# PCB-CMB-2b.net
KiCad netlist of a schematic drawn in EAGLE
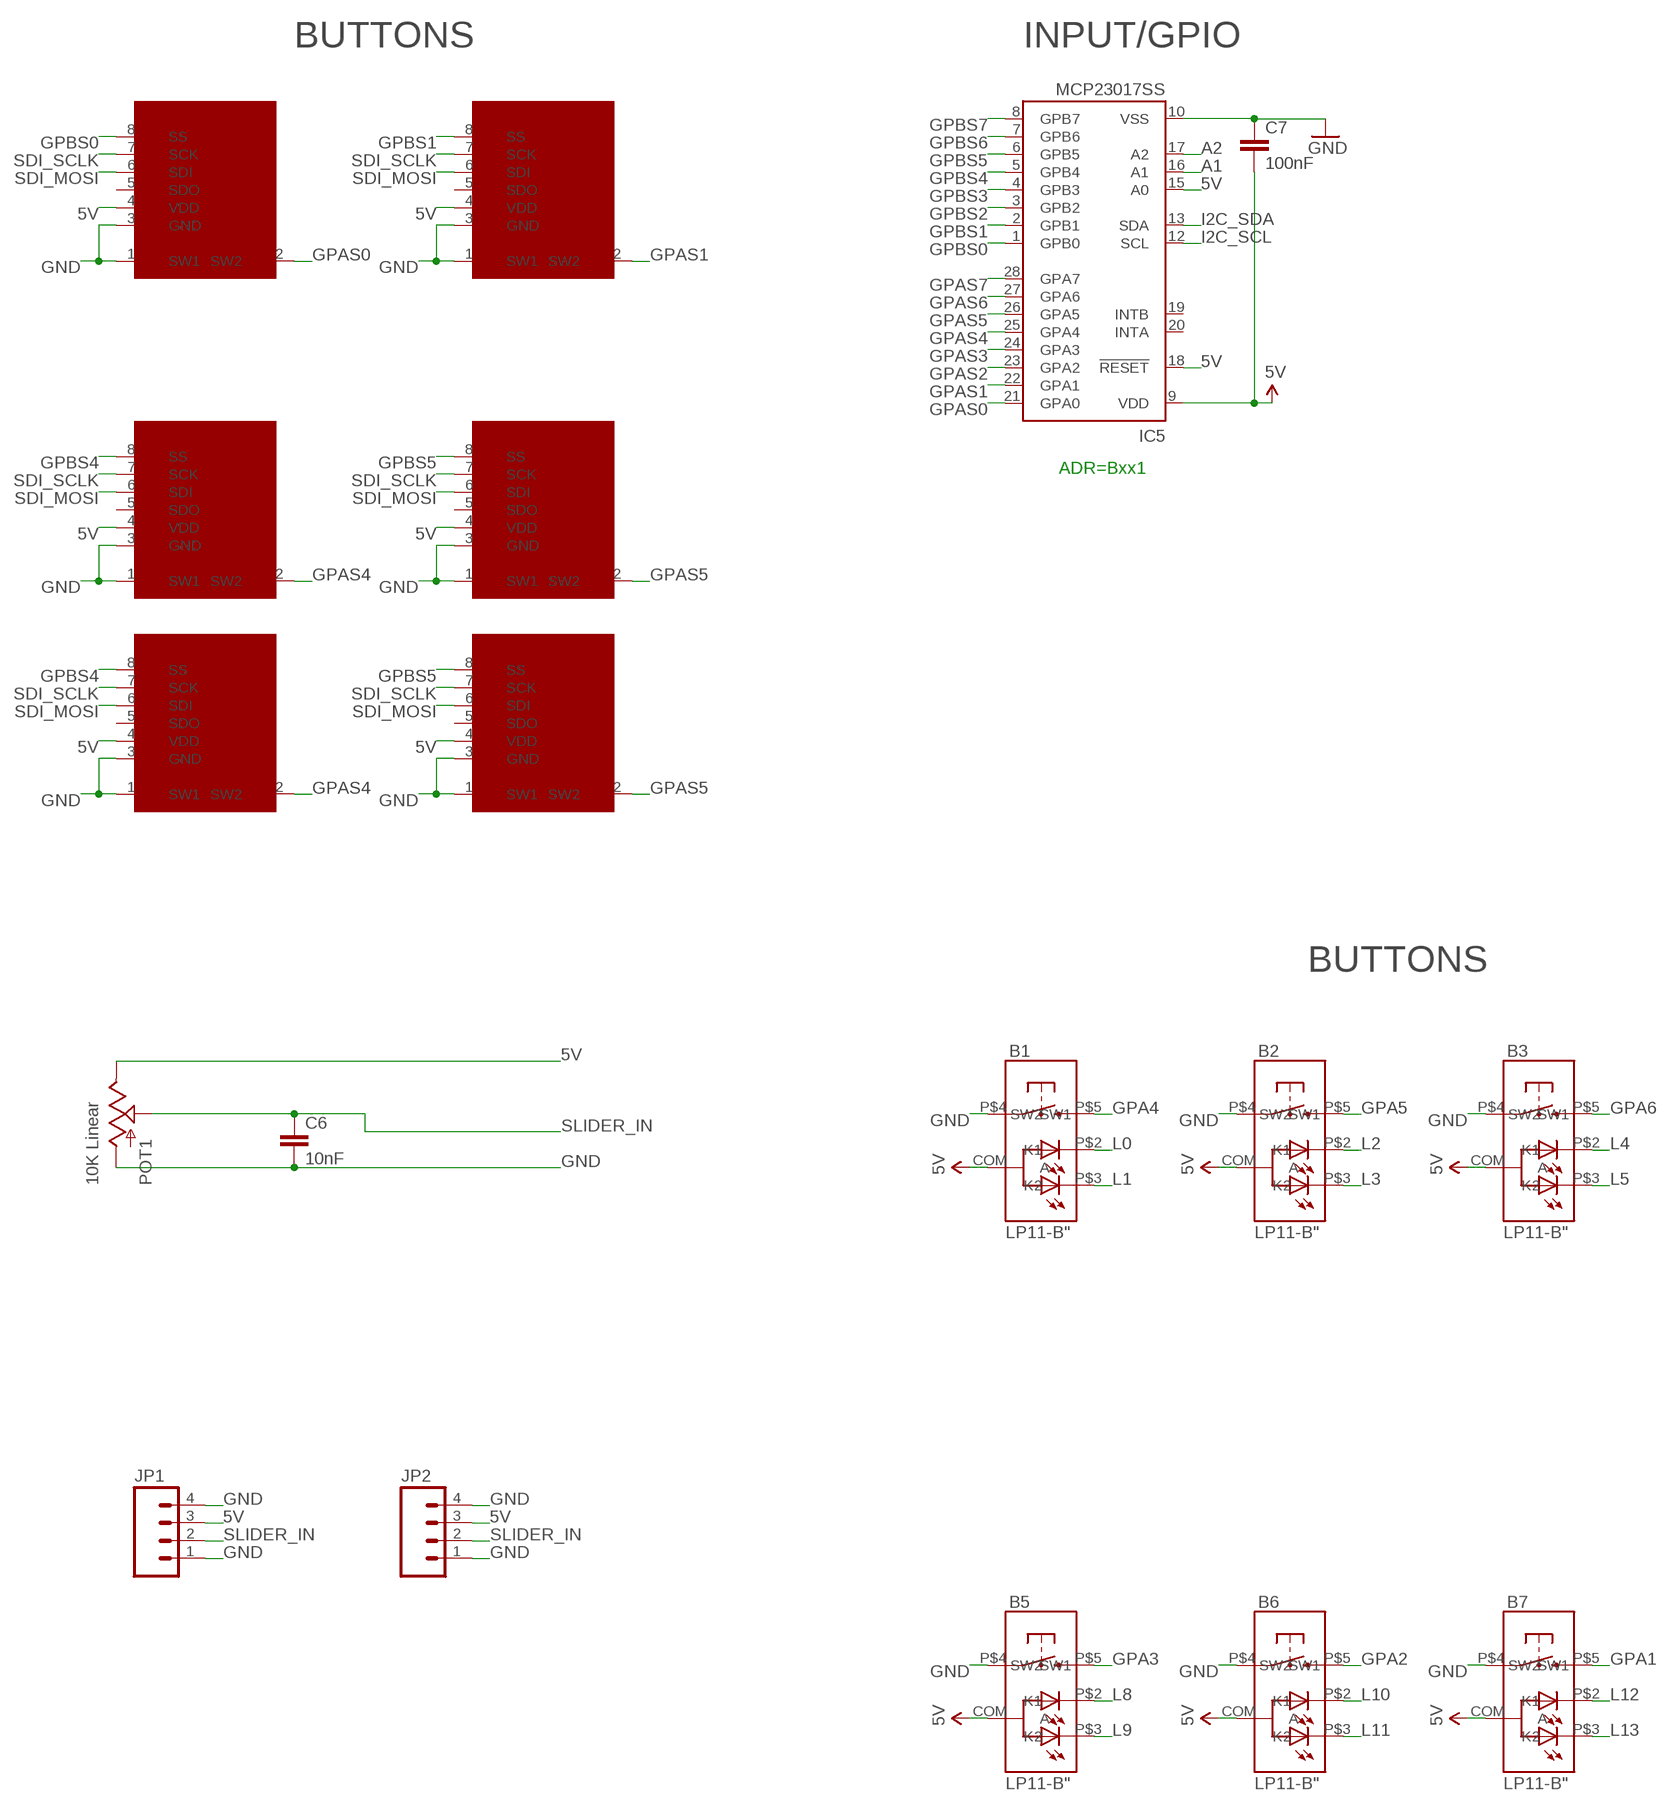
[diagram p0: schematic, sheet 1, part 1 of 2]
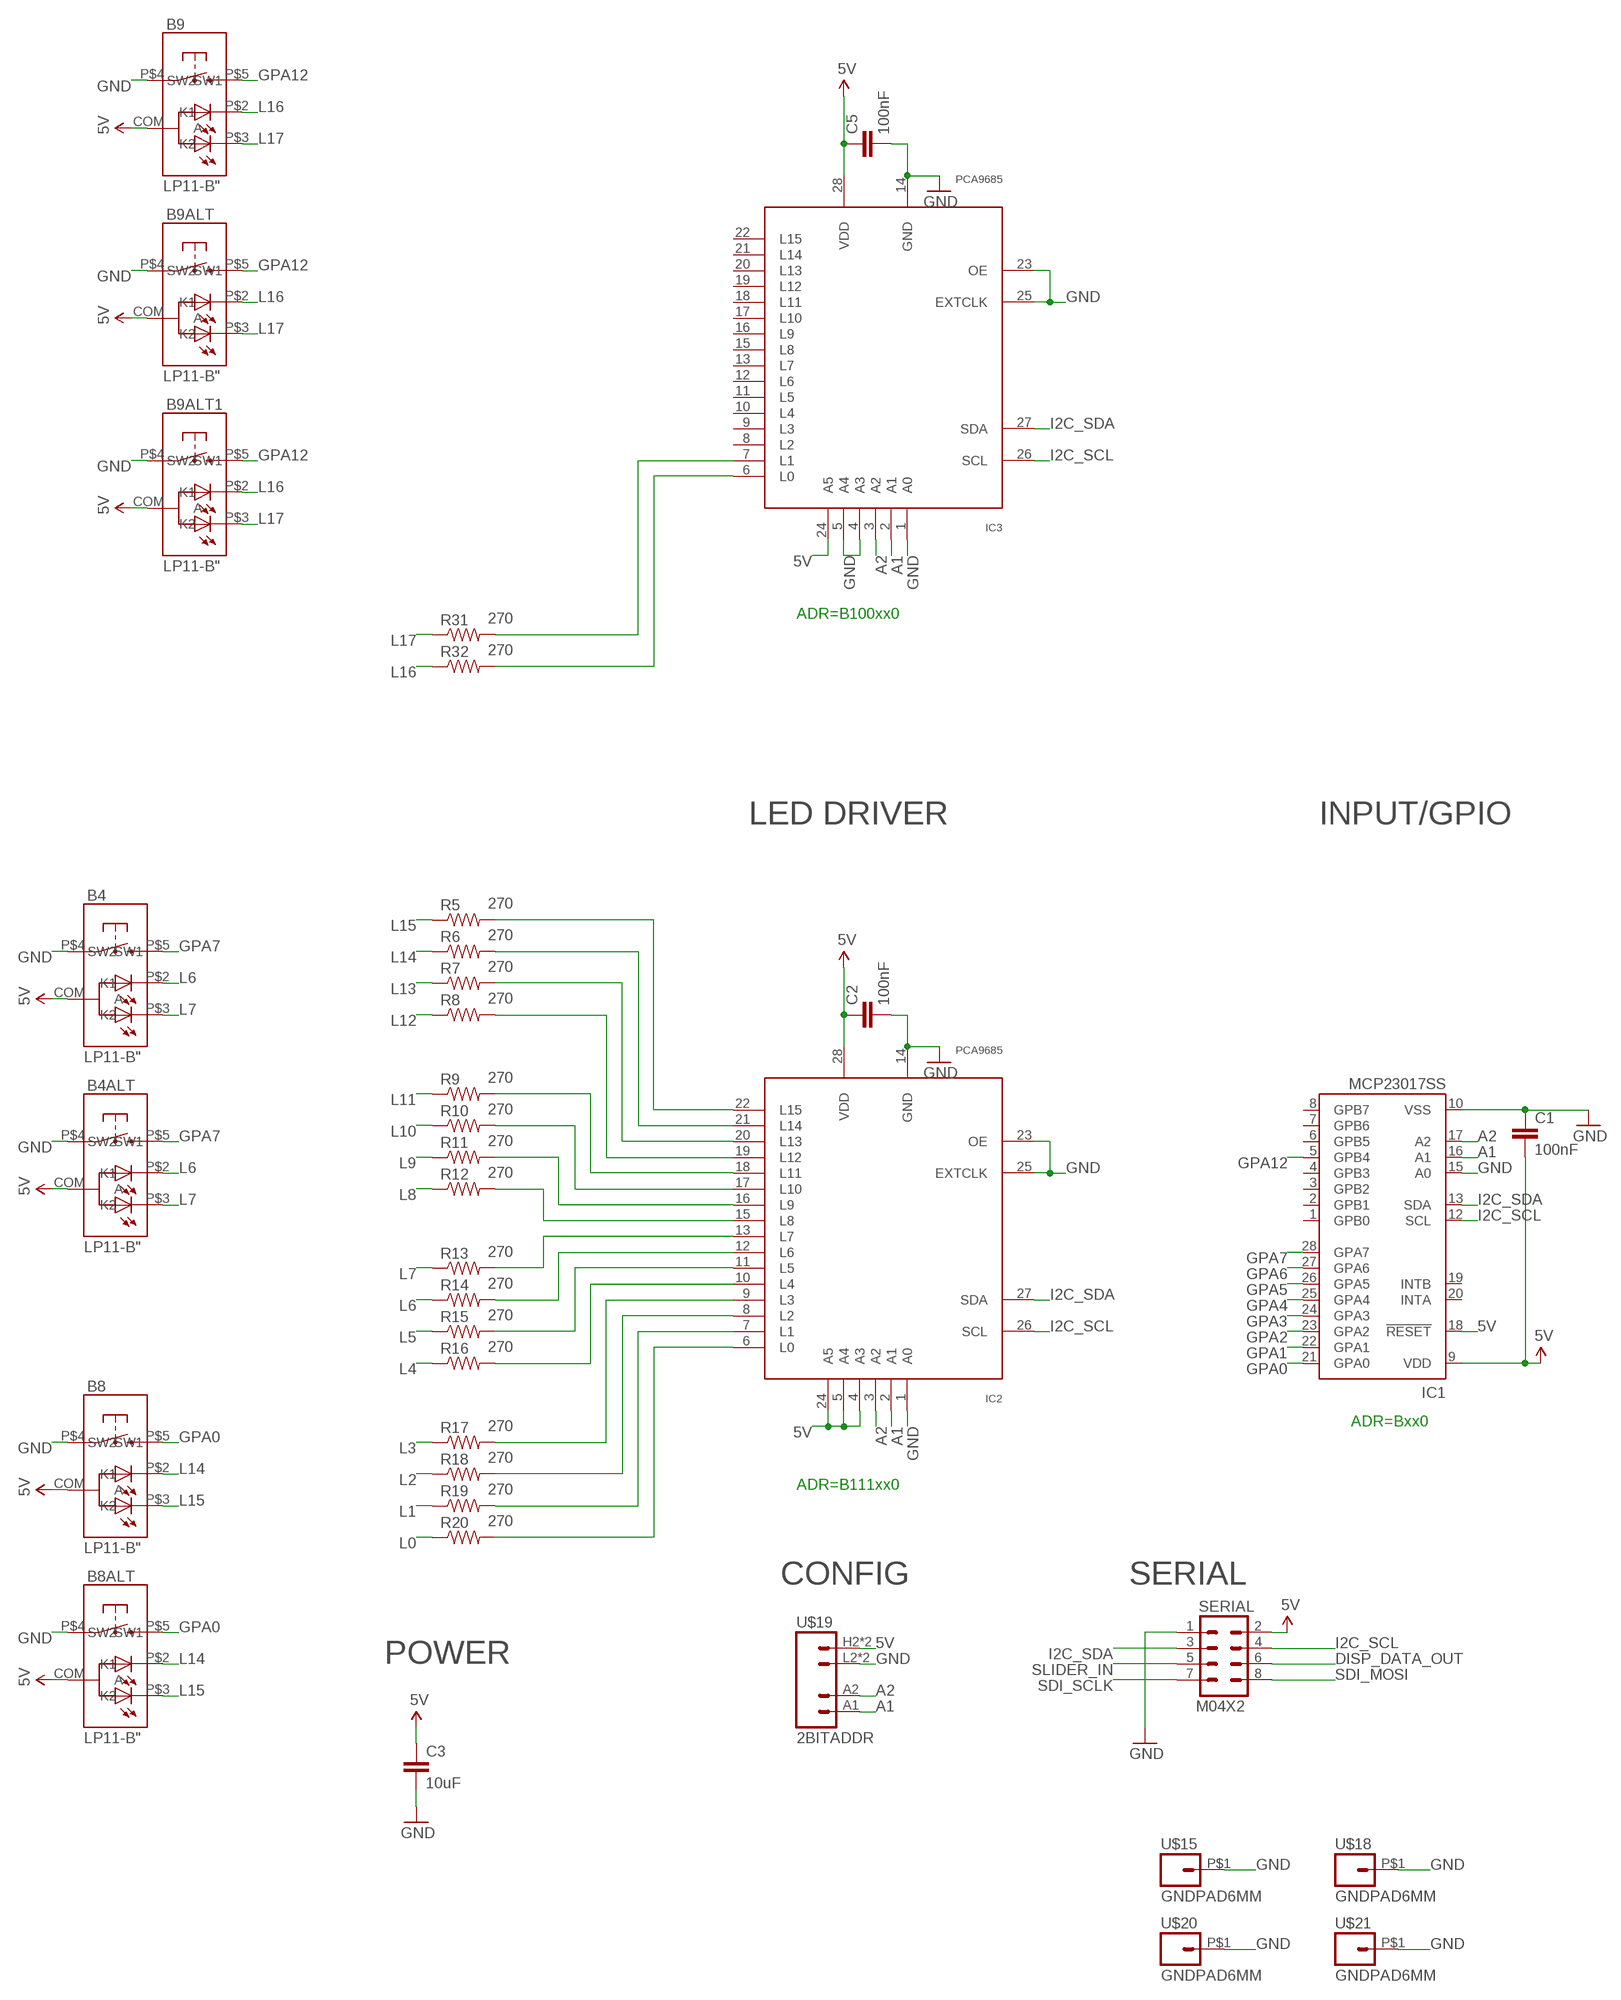
[diagram p1: schematic, sheet 1, part 2 of 2]

(export (version "E")
  (design (tool "Eeschema 10.0.6"))
  (components
    (comp (ref "B1")
      (value "LP11-B\"")
      (footprint "eagle-import:LP11")
      (libsource (lib "eagle-import") (part "LP11-B{dblquote}"))
    )
    (comp (ref "B2")
      (value "LP11-B\"")
      (footprint "eagle-import:LP11")
      (libsource (lib "eagle-import") (part "LP11-B{dblquote}"))
    )
    (comp (ref "B3")
      (value "LP11-B\"")
      (footprint "eagle-import:LP11")
      (libsource (lib "eagle-import") (part "LP11-B{dblquote}"))
    )
    (comp (ref "B4")
      (value "LP11-B\"")
      (footprint "eagle-import:LP11")
      (libsource (lib "eagle-import") (part "LP11-B{dblquote}"))
    )
    (comp (ref "B4ALT")
      (value "LP11-B\"")
      (footprint "eagle-import:LP11")
      (libsource (lib "eagle-import") (part "LP11-B{dblquote}"))
    )
    (comp (ref "B5")
      (value "LP11-B\"")
      (footprint "eagle-import:LP11")
      (libsource (lib "eagle-import") (part "LP11-B{dblquote}"))
    )
    (comp (ref "B6")
      (value "LP11-B\"")
      (footprint "eagle-import:LP11")
      (libsource (lib "eagle-import") (part "LP11-B{dblquote}"))
    )
    (comp (ref "B7")
      (value "LP11-B\"")
      (footprint "eagle-import:LP11")
      (libsource (lib "eagle-import") (part "LP11-B{dblquote}"))
    )
    (comp (ref "B8")
      (value "LP11-B\"")
      (footprint "eagle-import:LP11")
      (libsource (lib "eagle-import") (part "LP11-B{dblquote}"))
    )
    (comp (ref "B8ALT")
      (value "LP11-B\"")
      (footprint "eagle-import:LP11")
      (libsource (lib "eagle-import") (part "LP11-B{dblquote}"))
    )
    (comp (ref "B9")
      (value "LP11-B\"")
      (footprint "eagle-import:LP11")
      (libsource (lib "eagle-import") (part "LP11-B{dblquote}"))
    )
    (comp (ref "B9ALT")
      (value "LP11-B\"")
      (footprint "eagle-import:LP11")
      (libsource (lib "eagle-import") (part "LP11-B{dblquote}"))
    )
    (comp (ref "B9ALT1")
      (value "LP11-B\"")
      (footprint "eagle-import:LP11")
      (libsource (lib "eagle-import") (part "LP11-B{dblquote}"))
    )
    (comp (ref "C1")
      (value "100nF")
      (footprint "eagle-import:0603-CAP")
      (libsource (lib "eagle-import") (part "CAP0603-CAP"))
    )
    (comp (ref "C2")
      (value "100nF")
      (footprint "eagle-import:0603-CAP")
      (libsource (lib "eagle-import") (part "CAP0603-CAP"))
    )
    (comp (ref "C3")
      (value "10uF")
      (footprint "eagle-import:0805")
      (libsource (lib "eagle-import") (part "CAP0805"))
    )
    (comp (ref "C5")
      (value "100nF")
      (footprint "eagle-import:0603-CAP")
      (libsource (lib "eagle-import") (part "CAP0603-CAP"))
    )
    (comp (ref "C6")
      (value "10nF")
      (footprint "eagle-import:0603-CAP")
      (libsource (lib "eagle-import") (part "CAP0603-CAP"))
    )
    (comp (ref "C7")
      (value "100nF")
      (footprint "eagle-import:0603-CAP")
      (libsource (lib "eagle-import") (part "CAP0603-CAP"))
    )
    (comp (ref "IC1")
      (value "MCP23017SS")
      (footprint "eagle-import:SSOP28")
      (fields
        (field (name "MF") "MICROCHIP")
        (field (name "MPN") "MCP23017-E/SS")
        (field (name "MPN_1") "MCP23017-E/SS")
        (field (name "OC_FARNELL") "1467674")
        (field (name "OC_NEWARK") "31K2960")
      )
      (libsource (lib "eagle-import") (part "MCP23017SS"))
    )
    (comp (ref "IC2")
      (value "PCA9685")
      (footprint "eagle-import:TSSOP28")
      (libsource (lib "eagle-import") (part "PCA9685"))
    )
    (comp (ref "IC3")
      (value "PCA9685")
      (footprint "eagle-import:TSSOP28")
      (libsource (lib "eagle-import") (part "PCA9685"))
    )
    (comp (ref "IC5")
      (value "MCP23017SS")
      (footprint "eagle-import:SSOP28")
      (fields
        (field (name "MF") "MICROCHIP")
        (field (name "MPN") "MCP23017-E/SS")
        (field (name "MPN_1") "MCP23017-E/SS")
        (field (name "OC_FARNELL") "1467674")
        (field (name "OC_NEWARK") "31K2960")
      )
      (libsource (lib "eagle-import") (part "MCP23017SS"))
    )
    (comp (ref "JP1")
      (value "M04PTH")
      (footprint "eagle-import:1X04")
      (libsource (lib "eagle-import") (part "M04PTH"))
    )
    (comp (ref "JP2")
      (value "M04PTH")
      (footprint "eagle-import:1X04")
      (libsource (lib "eagle-import") (part "M04PTH"))
    )
    (comp (ref "POT1")
      (value "10K Linear")
      (footprint "eagle-import:SLIDER20")
      (libsource (lib "eagle-import") (part "SLIDER20"))
    )
    (comp (ref "R5")
      (value "270")
      (footprint "eagle-import:0603-RES")
      (libsource (lib "eagle-import") (part "RESISTOR0603-RES"))
    )
    (comp (ref "R6")
      (value "270")
      (footprint "eagle-import:0603-RES")
      (libsource (lib "eagle-import") (part "RESISTOR0603-RES"))
    )
    (comp (ref "R7")
      (value "270")
      (footprint "eagle-import:0603-RES")
      (libsource (lib "eagle-import") (part "RESISTOR0603-RES"))
    )
    (comp (ref "R8")
      (value "270")
      (footprint "eagle-import:0603-RES")
      (libsource (lib "eagle-import") (part "RESISTOR0603-RES"))
    )
    (comp (ref "R9")
      (value "270")
      (footprint "eagle-import:0603-RES")
      (libsource (lib "eagle-import") (part "RESISTOR0603-RES"))
    )
    (comp (ref "R10")
      (value "270")
      (footprint "eagle-import:0603-RES")
      (libsource (lib "eagle-import") (part "RESISTOR0603-RES"))
    )
    (comp (ref "R11")
      (value "270")
      (footprint "eagle-import:0603-RES")
      (libsource (lib "eagle-import") (part "RESISTOR0603-RES"))
    )
    (comp (ref "R12")
      (value "270")
      (footprint "eagle-import:0603-RES")
      (libsource (lib "eagle-import") (part "RESISTOR0603-RES"))
    )
    (comp (ref "R13")
      (value "270")
      (footprint "eagle-import:0603-RES")
      (libsource (lib "eagle-import") (part "RESISTOR0603-RES"))
    )
    (comp (ref "R14")
      (value "270")
      (footprint "eagle-import:0603-RES")
      (libsource (lib "eagle-import") (part "RESISTOR0603-RES"))
    )
    (comp (ref "R15")
      (value "270")
      (footprint "eagle-import:0603-RES")
      (libsource (lib "eagle-import") (part "RESISTOR0603-RES"))
    )
    (comp (ref "R16")
      (value "270")
      (footprint "eagle-import:0603-RES")
      (libsource (lib "eagle-import") (part "RESISTOR0603-RES"))
    )
    (comp (ref "R17")
      (value "270")
      (footprint "eagle-import:0603-RES")
      (libsource (lib "eagle-import") (part "RESISTOR0603-RES"))
    )
    (comp (ref "R18")
      (value "270")
      (footprint "eagle-import:0603-RES")
      (libsource (lib "eagle-import") (part "RESISTOR0603-RES"))
    )
    (comp (ref "R19")
      (value "270")
      (footprint "eagle-import:0603-RES")
      (libsource (lib "eagle-import") (part "RESISTOR0603-RES"))
    )
    (comp (ref "R20")
      (value "270")
      (footprint "eagle-import:0603-RES")
      (libsource (lib "eagle-import") (part "RESISTOR0603-RES"))
    )
    (comp (ref "R31")
      (value "270")
      (footprint "eagle-import:0603-RES")
      (libsource (lib "eagle-import") (part "RESISTOR0603-RES"))
    )
    (comp (ref "R32")
      (value "270")
      (footprint "eagle-import:0603-RES")
      (libsource (lib "eagle-import") (part "RESISTOR0603-RES"))
    )
    (comp (ref "SERIAL")
      (value "M04X2")
      (footprint "eagle-import:2X4")
      (libsource (lib "eagle-import") (part "M04X2"))
    )
    (comp (ref "SSW1")
      (value "SMART_SWITCHSMART_SWITCH_8PIN")
      (footprint "eagle-import:SMART_SWITCH")
      (libsource (lib "eagle-import") (part "SMART_SWITCHSMART_SWITCH_8PIN"))
    )
    (comp (ref "SSW2")
      (value "SMART_SWITCHSMART_SWITCH_8PIN")
      (footprint "eagle-import:SMART_SWITCH")
      (libsource (lib "eagle-import") (part "SMART_SWITCHSMART_SWITCH_8PIN"))
    )
    (comp (ref "SSW5")
      (value "SMART_SWITCHSMART_SWITCH_8PIN")
      (footprint "eagle-import:SMART_SWITCH")
      (libsource (lib "eagle-import") (part "SMART_SWITCHSMART_SWITCH_8PIN"))
    )
    (comp (ref "SSW5ALT")
      (value "SMART_SWITCHSMART_SWITCH_8PIN")
      (footprint "eagle-import:SMART_SWITCH")
      (libsource (lib "eagle-import") (part "SMART_SWITCHSMART_SWITCH_8PIN"))
    )
    (comp (ref "SSW6")
      (value "SMART_SWITCHSMART_SWITCH_8PIN")
      (footprint "eagle-import:SMART_SWITCH")
      (libsource (lib "eagle-import") (part "SMART_SWITCHSMART_SWITCH_8PIN"))
    )
    (comp (ref "SSW6ALT")
      (value "SMART_SWITCHSMART_SWITCH_8PIN")
      (footprint "eagle-import:SMART_SWITCH")
      (libsource (lib "eagle-import") (part "SMART_SWITCHSMART_SWITCH_8PIN"))
    )
    (comp (ref "U$15")
      (value "GNDPAD6MM")
      (footprint "eagle-import:3.2MMPAD6MM")
      (libsource (lib "eagle-import") (part "GNDPAD6MM"))
    )
    (comp (ref "U$18")
      (value "GNDPAD6MM")
      (footprint "eagle-import:3.2MMPAD6MM")
      (libsource (lib "eagle-import") (part "GNDPAD6MM"))
    )
    (comp (ref "U$19")
      (value "2BITADDR")
      (footprint "eagle-import:2BITADDR")
      (libsource (lib "eagle-import") (part "2BITADDR"))
    )
    (comp (ref "U$20")
      (value "GNDPAD6MM")
      (footprint "eagle-import:3.2MMPAD6MM")
      (libsource (lib "eagle-import") (part "GNDPAD6MM"))
    )
    (comp (ref "U$21")
      (value "GNDPAD6MM")
      (footprint "eagle-import:3.2MMPAD6MM")
      (libsource (lib "eagle-import") (part "GNDPAD6MM"))
    )
  )
  (nets
    (net (code "1") (name "5V") (class "Default")
      (node (ref "B1") (pin "COM") (pinfunction "A_COM") (pintype "bidirectional"))
      (node (ref "B2") (pin "COM") (pinfunction "A_COM") (pintype "bidirectional"))
      (node (ref "B3") (pin "COM") (pinfunction "A_COM") (pintype "bidirectional"))
      (node (ref "B4") (pin "COM") (pinfunction "A_COM") (pintype "bidirectional"))
      (node (ref "B4ALT") (pin "COM") (pinfunction "A_COM") (pintype "bidirectional"))
      (node (ref "B5") (pin "COM") (pinfunction "A_COM") (pintype "bidirectional"))
      (node (ref "B6") (pin "COM") (pinfunction "A_COM") (pintype "bidirectional"))
      (node (ref "B7") (pin "COM") (pinfunction "A_COM") (pintype "bidirectional"))
      (node (ref "B8") (pin "COM") (pinfunction "A_COM") (pintype "bidirectional"))
      (node (ref "B8ALT") (pin "COM") (pinfunction "A_COM") (pintype "bidirectional"))
      (node (ref "B9") (pin "COM") (pinfunction "A_COM") (pintype "bidirectional"))
      (node (ref "B9ALT") (pin "COM") (pinfunction "A_COM") (pintype "bidirectional"))
      (node (ref "B9ALT1") (pin "COM") (pinfunction "A_COM") (pintype "bidirectional"))
      (node (ref "C1") (pin "2") (pinfunction "2_2") (pintype "passive"))
      (node (ref "C2") (pin "1") (pinfunction "1_1") (pintype "passive"))
      (node (ref "C3") (pin "1") (pinfunction "1_1") (pintype "passive"))
      (node (ref "C5") (pin "1") (pinfunction "1_1") (pintype "passive"))
      (node (ref "C7") (pin "2") (pinfunction "2_2") (pintype "passive"))
      (node (ref "IC1") (pin "18") (pinfunction "~{RESET}_18") (pintype "input"))
      (node (ref "IC1") (pin "9") (pinfunction "VDD_9") (pintype "power_in"))
      (node (ref "IC2") (pin "24") (pinfunction "A5_24") (pintype "input"))
      (node (ref "IC2") (pin "28") (pinfunction "VDD_28") (pintype "power_in"))
      (node (ref "IC2") (pin "4") (pinfunction "A3_4") (pintype "input"))
      (node (ref "IC2") (pin "5") (pinfunction "A4_5") (pintype "input"))
      (node (ref "IC3") (pin "24") (pinfunction "A5_24") (pintype "input"))
      (node (ref "IC3") (pin "28") (pinfunction "VDD_28") (pintype "power_in"))
      (node (ref "IC5") (pin "15") (pinfunction "A0_15") (pintype "input"))
      (node (ref "IC5") (pin "18") (pinfunction "~{RESET}_18") (pintype "input"))
      (node (ref "IC5") (pin "9") (pinfunction "VDD_9") (pintype "power_in"))
      (node (ref "JP1") (pin "3") (pinfunction "3_3") (pintype "passive"))
      (node (ref "JP2") (pin "3") (pinfunction "3_3") (pintype "passive"))
      (node (ref "POT1") (pin "1") (pinfunction "E_1") (pintype "passive"))
      (node (ref "SERIAL") (pin "2") (pinfunction "2_2") (pintype "passive"))
      (node (ref "SSW1") (pin "4") (pinfunction "VDD_4") (pintype "bidirectional"))
      (node (ref "SSW2") (pin "4") (pinfunction "VDD_4") (pintype "bidirectional"))
      (node (ref "SSW5") (pin "4") (pinfunction "VDD_4") (pintype "bidirectional"))
      (node (ref "SSW5ALT") (pin "4") (pinfunction "VDD_4") (pintype "bidirectional"))
      (node (ref "SSW6") (pin "4") (pinfunction "VDD_4") (pintype "bidirectional"))
      (node (ref "SSW6ALT") (pin "4") (pinfunction "VDD_4") (pintype "bidirectional"))
      (node (ref "U$19") (pin "H2") (pinfunction "VCC_H2") (pintype "passive"))
      (node (ref "U$19") (pin "H3") (pinfunction "VCC_H3") (pintype "passive"))
    )
    (net (code "2") (name "A1") (class "Default")
      (node (ref "IC1") (pin "16") (pinfunction "A1_16") (pintype "input"))
      (node (ref "IC2") (pin "2") (pinfunction "A1_2") (pintype "input"))
      (node (ref "IC3") (pin "2") (pinfunction "A1_2") (pintype "input"))
      (node (ref "IC5") (pin "16") (pinfunction "A1_16") (pintype "input"))
      (node (ref "U$19") (pin "A1") (pinfunction "A1_A1") (pintype "passive"))
    )
    (net (code "3") (name "A2") (class "Default")
      (node (ref "IC1") (pin "17") (pinfunction "A2_17") (pintype "input"))
      (node (ref "IC2") (pin "3") (pinfunction "A2_3") (pintype "input"))
      (node (ref "IC3") (pin "3") (pinfunction "A2_3") (pintype "input"))
      (node (ref "IC5") (pin "17") (pinfunction "A2_17") (pintype "input"))
      (node (ref "U$19") (pin "A2") (pinfunction "A2_A2") (pintype "passive"))
    )
    (net (code "4") (name "DISP_DATA_OUT") (class "Default")
      (node (ref "SERIAL") (pin "6") (pinfunction "6_6") (pintype "passive"))
    )
    (net (code "5") (name "GND") (class "Default")
      (node (ref "B1") (pin "P$4") (pinfunction "SW1_P$4") (pintype "bidirectional"))
      (node (ref "B2") (pin "P$4") (pinfunction "SW1_P$4") (pintype "bidirectional"))
      (node (ref "B3") (pin "P$4") (pinfunction "SW1_P$4") (pintype "bidirectional"))
      (node (ref "B4") (pin "P$4") (pinfunction "SW1_P$4") (pintype "bidirectional"))
      (node (ref "B4ALT") (pin "P$4") (pinfunction "SW1_P$4") (pintype "bidirectional"))
      (node (ref "B5") (pin "P$4") (pinfunction "SW1_P$4") (pintype "bidirectional"))
      (node (ref "B6") (pin "P$4") (pinfunction "SW1_P$4") (pintype "bidirectional"))
      (node (ref "B7") (pin "P$4") (pinfunction "SW1_P$4") (pintype "bidirectional"))
      (node (ref "B8") (pin "P$4") (pinfunction "SW1_P$4") (pintype "bidirectional"))
      (node (ref "B8ALT") (pin "P$4") (pinfunction "SW1_P$4") (pintype "bidirectional"))
      (node (ref "B9") (pin "P$4") (pinfunction "SW1_P$4") (pintype "bidirectional"))
      (node (ref "B9ALT") (pin "P$4") (pinfunction "SW1_P$4") (pintype "bidirectional"))
      (node (ref "B9ALT1") (pin "P$4") (pinfunction "SW1_P$4") (pintype "bidirectional"))
      (node (ref "C1") (pin "1") (pinfunction "1_1") (pintype "passive"))
      (node (ref "C2") (pin "2") (pinfunction "2_2") (pintype "passive"))
      (node (ref "C3") (pin "2") (pinfunction "2_2") (pintype "passive"))
      (node (ref "C5") (pin "2") (pinfunction "2_2") (pintype "passive"))
      (node (ref "C6") (pin "2") (pinfunction "2_2") (pintype "passive"))
      (node (ref "C7") (pin "1") (pinfunction "1_1") (pintype "passive"))
      (node (ref "IC1") (pin "10") (pinfunction "VSS_10") (pintype "power_in"))
      (node (ref "IC1") (pin "15") (pinfunction "A0_15") (pintype "input"))
      (node (ref "IC2") (pin "1") (pinfunction "A0_1") (pintype "input"))
      (node (ref "IC2") (pin "14") (pinfunction "GND_14") (pintype "power_in"))
      (node (ref "IC2") (pin "23") (pinfunction "OE_23") (pintype "input"))
      (node (ref "IC2") (pin "25") (pinfunction "EXTCLK_25") (pintype "input"))
      (node (ref "IC3") (pin "1") (pinfunction "A0_1") (pintype "input"))
      (node (ref "IC3") (pin "14") (pinfunction "GND_14") (pintype "power_in"))
      (node (ref "IC3") (pin "23") (pinfunction "OE_23") (pintype "input"))
      (node (ref "IC3") (pin "25") (pinfunction "EXTCLK_25") (pintype "input"))
      (node (ref "IC3") (pin "4") (pinfunction "A3_4") (pintype "input"))
      (node (ref "IC3") (pin "5") (pinfunction "A4_5") (pintype "input"))
      (node (ref "IC5") (pin "10") (pinfunction "VSS_10") (pintype "power_in"))
      (node (ref "JP1") (pin "1") (pinfunction "1_1") (pintype "passive"))
      (node (ref "JP1") (pin "4") (pinfunction "4_4") (pintype "passive"))
      (node (ref "JP2") (pin "1") (pinfunction "1_1") (pintype "passive"))
      (node (ref "JP2") (pin "4") (pinfunction "4_4") (pintype "passive"))
      (node (ref "POT1") (pin "3") (pinfunction "A_3") (pintype "passive"))
      (node (ref "SERIAL") (pin "1") (pinfunction "1_1") (pintype "passive"))
      (node (ref "SSW1") (pin "1") (pinfunction "SW1_1") (pintype "bidirectional"))
      (node (ref "SSW1") (pin "3") (pinfunction "GND_3") (pintype "bidirectional"))
      (node (ref "SSW2") (pin "1") (pinfunction "SW1_1") (pintype "bidirectional"))
      (node (ref "SSW2") (pin "3") (pinfunction "GND_3") (pintype "bidirectional"))
      (node (ref "SSW5") (pin "1") (pinfunction "SW1_1") (pintype "bidirectional"))
      (node (ref "SSW5") (pin "3") (pinfunction "GND_3") (pintype "bidirectional"))
      (node (ref "SSW5ALT") (pin "1") (pinfunction "SW1_1") (pintype "bidirectional"))
      (node (ref "SSW5ALT") (pin "3") (pinfunction "GND_3") (pintype "bidirectional"))
      (node (ref "SSW6") (pin "1") (pinfunction "SW1_1") (pintype "bidirectional"))
      (node (ref "SSW6") (pin "3") (pinfunction "GND_3") (pintype "bidirectional"))
      (node (ref "SSW6ALT") (pin "1") (pinfunction "SW1_1") (pintype "bidirectional"))
      (node (ref "SSW6ALT") (pin "3") (pinfunction "GND_3") (pintype "bidirectional"))
      (node (ref "U$15") (pin "P$1") (pinfunction "1_P$1") (pintype "passive"))
      (node (ref "U$18") (pin "P$1") (pinfunction "1_P$1") (pintype "passive"))
      (node (ref "U$19") (pin "L2") (pinfunction "GND_L2") (pintype "passive"))
      (node (ref "U$19") (pin "L3") (pinfunction "GND_L3") (pintype "passive"))
      (node (ref "U$20") (pin "P$1") (pinfunction "1_P$1") (pintype "passive"))
      (node (ref "U$21") (pin "P$1") (pinfunction "1_P$1") (pintype "passive"))
    )
    (net (code "6") (name "GPA0") (class "Default")
      (node (ref "B8") (pin "P$5") (pinfunction "SW2_P$5") (pintype "bidirectional"))
      (node (ref "B8ALT") (pin "P$5") (pinfunction "SW2_P$5") (pintype "bidirectional"))
      (node (ref "IC1") (pin "21") (pinfunction "GPA0_21") (pintype "bidirectional"))
    )
    (net (code "7") (name "GPA1") (class "Default")
      (node (ref "B7") (pin "P$5") (pinfunction "SW2_P$5") (pintype "bidirectional"))
      (node (ref "IC1") (pin "22") (pinfunction "GPA1_22") (pintype "bidirectional"))
    )
    (net (code "8") (name "GPA2") (class "Default")
      (node (ref "B6") (pin "P$5") (pinfunction "SW2_P$5") (pintype "bidirectional"))
      (node (ref "IC1") (pin "23") (pinfunction "GPA2_23") (pintype "bidirectional"))
    )
    (net (code "9") (name "GPA3") (class "Default")
      (node (ref "B5") (pin "P$5") (pinfunction "SW2_P$5") (pintype "bidirectional"))
      (node (ref "IC1") (pin "24") (pinfunction "GPA3_24") (pintype "bidirectional"))
    )
    (net (code "10") (name "GPA4") (class "Default")
      (node (ref "B1") (pin "P$5") (pinfunction "SW2_P$5") (pintype "bidirectional"))
      (node (ref "IC1") (pin "25") (pinfunction "GPA4_25") (pintype "bidirectional"))
    )
    (net (code "11") (name "GPA5") (class "Default")
      (node (ref "B2") (pin "P$5") (pinfunction "SW2_P$5") (pintype "bidirectional"))
      (node (ref "IC1") (pin "26") (pinfunction "GPA5_26") (pintype "bidirectional"))
    )
    (net (code "12") (name "GPA6") (class "Default")
      (node (ref "B3") (pin "P$5") (pinfunction "SW2_P$5") (pintype "bidirectional"))
      (node (ref "IC1") (pin "27") (pinfunction "GPA6_27") (pintype "bidirectional"))
    )
    (net (code "13") (name "GPA7") (class "Default")
      (node (ref "B4") (pin "P$5") (pinfunction "SW2_P$5") (pintype "bidirectional"))
      (node (ref "B4ALT") (pin "P$5") (pinfunction "SW2_P$5") (pintype "bidirectional"))
      (node (ref "IC1") (pin "28") (pinfunction "GPA7_28") (pintype "bidirectional"))
    )
    (net (code "14") (name "GPA12") (class "Default")
      (node (ref "B9") (pin "P$5") (pinfunction "SW2_P$5") (pintype "bidirectional"))
      (node (ref "B9ALT") (pin "P$5") (pinfunction "SW2_P$5") (pintype "bidirectional"))
      (node (ref "B9ALT1") (pin "P$5") (pinfunction "SW2_P$5") (pintype "bidirectional"))
      (node (ref "IC1") (pin "5") (pinfunction "GPB4_5") (pintype "bidirectional"))
    )
    (net (code "15") (name "GPAS0") (class "Default")
      (node (ref "IC5") (pin "21") (pinfunction "GPA0_21") (pintype "bidirectional"))
      (node (ref "SSW1") (pin "2") (pinfunction "SW2_2") (pintype "bidirectional"))
    )
    (net (code "16") (name "GPAS1") (class "Default")
      (node (ref "IC5") (pin "22") (pinfunction "GPA1_22") (pintype "bidirectional"))
      (node (ref "SSW2") (pin "2") (pinfunction "SW2_2") (pintype "bidirectional"))
    )
    (net (code "17") (name "GPAS2") (class "Default")
      (node (ref "IC5") (pin "23") (pinfunction "GPA2_23") (pintype "bidirectional"))
    )
    (net (code "18") (name "GPAS3") (class "Default")
      (node (ref "IC5") (pin "24") (pinfunction "GPA3_24") (pintype "bidirectional"))
    )
    (net (code "19") (name "GPAS4") (class "Default")
      (node (ref "IC5") (pin "25") (pinfunction "GPA4_25") (pintype "bidirectional"))
      (node (ref "SSW5") (pin "2") (pinfunction "SW2_2") (pintype "bidirectional"))
      (node (ref "SSW5ALT") (pin "2") (pinfunction "SW2_2") (pintype "bidirectional"))
    )
    (net (code "20") (name "GPAS5") (class "Default")
      (node (ref "IC5") (pin "26") (pinfunction "GPA5_26") (pintype "bidirectional"))
      (node (ref "SSW6") (pin "2") (pinfunction "SW2_2") (pintype "bidirectional"))
      (node (ref "SSW6ALT") (pin "2") (pinfunction "SW2_2") (pintype "bidirectional"))
    )
    (net (code "21") (name "GPAS6") (class "Default")
      (node (ref "IC5") (pin "27") (pinfunction "GPA6_27") (pintype "bidirectional"))
    )
    (net (code "22") (name "GPAS7") (class "Default")
      (node (ref "IC5") (pin "28") (pinfunction "GPA7_28") (pintype "bidirectional"))
    )
    (net (code "23") (name "GPBS0") (class "Default")
      (node (ref "IC5") (pin "1") (pinfunction "GPB0_1") (pintype "bidirectional"))
      (node (ref "SSW1") (pin "8") (pinfunction "SS_8") (pintype "bidirectional"))
    )
    (net (code "24") (name "GPBS1") (class "Default")
      (node (ref "IC5") (pin "2") (pinfunction "GPB1_2") (pintype "bidirectional"))
      (node (ref "SSW2") (pin "8") (pinfunction "SS_8") (pintype "bidirectional"))
    )
    (net (code "25") (name "GPBS2") (class "Default")
      (node (ref "IC5") (pin "3") (pinfunction "GPB2_3") (pintype "bidirectional"))
    )
    (net (code "26") (name "GPBS3") (class "Default")
      (node (ref "IC5") (pin "4") (pinfunction "GPB3_4") (pintype "bidirectional"))
    )
    (net (code "27") (name "GPBS4") (class "Default")
      (node (ref "IC5") (pin "5") (pinfunction "GPB4_5") (pintype "bidirectional"))
      (node (ref "SSW5") (pin "8") (pinfunction "SS_8") (pintype "bidirectional"))
      (node (ref "SSW5ALT") (pin "8") (pinfunction "SS_8") (pintype "bidirectional"))
    )
    (net (code "28") (name "GPBS5") (class "Default")
      (node (ref "IC5") (pin "6") (pinfunction "GPB5_6") (pintype "bidirectional"))
      (node (ref "SSW6") (pin "8") (pinfunction "SS_8") (pintype "bidirectional"))
      (node (ref "SSW6ALT") (pin "8") (pinfunction "SS_8") (pintype "bidirectional"))
    )
    (net (code "29") (name "GPBS6") (class "Default")
      (node (ref "IC5") (pin "7") (pinfunction "GPB6_7") (pintype "bidirectional"))
    )
    (net (code "30") (name "GPBS7") (class "Default")
      (node (ref "IC5") (pin "8") (pinfunction "GPB7_8") (pintype "bidirectional"))
    )
    (net (code "31") (name "I2C_SCL") (class "Default")
      (node (ref "IC1") (pin "12") (pinfunction "SCL_12") (pintype "input"))
      (node (ref "IC2") (pin "26") (pinfunction "SCL_26") (pintype "input"))
      (node (ref "IC3") (pin "26") (pinfunction "SCL_26") (pintype "input"))
      (node (ref "IC5") (pin "12") (pinfunction "SCL_12") (pintype "input"))
      (node (ref "SERIAL") (pin "4") (pinfunction "4_4") (pintype "passive"))
    )
    (net (code "32") (name "I2C_SDA") (class "Default")
      (node (ref "IC1") (pin "13") (pinfunction "SDA_13") (pintype "bidirectional"))
      (node (ref "IC2") (pin "27") (pinfunction "SDA_27") (pintype "input"))
      (node (ref "IC3") (pin "27") (pinfunction "SDA_27") (pintype "input"))
      (node (ref "IC5") (pin "13") (pinfunction "SDA_13") (pintype "bidirectional"))
      (node (ref "SERIAL") (pin "3") (pinfunction "3_3") (pintype "passive"))
    )
    (net (code "33") (name "L0") (class "Default")
      (node (ref "B1") (pin "P$2") (pinfunction "K1_P$2") (pintype "bidirectional"))
      (node (ref "R20") (pin "1") (pinfunction "1_1") (pintype "passive"))
    )
    (net (code "34") (name "L1") (class "Default")
      (node (ref "B1") (pin "P$3") (pinfunction "K2_P$3") (pintype "bidirectional"))
      (node (ref "R19") (pin "1") (pinfunction "1_1") (pintype "passive"))
    )
    (net (code "35") (name "L2") (class "Default")
      (node (ref "B2") (pin "P$2") (pinfunction "K1_P$2") (pintype "bidirectional"))
      (node (ref "R18") (pin "1") (pinfunction "1_1") (pintype "passive"))
    )
    (net (code "36") (name "L3") (class "Default")
      (node (ref "B2") (pin "P$3") (pinfunction "K2_P$3") (pintype "bidirectional"))
      (node (ref "R17") (pin "1") (pinfunction "1_1") (pintype "passive"))
    )
    (net (code "37") (name "L4") (class "Default")
      (node (ref "B3") (pin "P$2") (pinfunction "K1_P$2") (pintype "bidirectional"))
      (node (ref "R16") (pin "1") (pinfunction "1_1") (pintype "passive"))
    )
    (net (code "38") (name "L5") (class "Default")
      (node (ref "B3") (pin "P$3") (pinfunction "K2_P$3") (pintype "bidirectional"))
      (node (ref "R15") (pin "1") (pinfunction "1_1") (pintype "passive"))
    )
    (net (code "39") (name "L6") (class "Default")
      (node (ref "B4") (pin "P$2") (pinfunction "K1_P$2") (pintype "bidirectional"))
      (node (ref "B4ALT") (pin "P$2") (pinfunction "K1_P$2") (pintype "bidirectional"))
      (node (ref "R14") (pin "1") (pinfunction "1_1") (pintype "passive"))
    )
    (net (code "40") (name "L7") (class "Default")
      (node (ref "B4") (pin "P$3") (pinfunction "K2_P$3") (pintype "bidirectional"))
      (node (ref "B4ALT") (pin "P$3") (pinfunction "K2_P$3") (pintype "bidirectional"))
      (node (ref "R13") (pin "1") (pinfunction "1_1") (pintype "passive"))
    )
    (net (code "41") (name "L8") (class "Default")
      (node (ref "B5") (pin "P$2") (pinfunction "K1_P$2") (pintype "bidirectional"))
      (node (ref "R12") (pin "1") (pinfunction "1_1") (pintype "passive"))
    )
    (net (code "42") (name "L9") (class "Default")
      (node (ref "B5") (pin "P$3") (pinfunction "K2_P$3") (pintype "bidirectional"))
      (node (ref "R11") (pin "1") (pinfunction "1_1") (pintype "passive"))
    )
    (net (code "43") (name "L10") (class "Default")
      (node (ref "B6") (pin "P$2") (pinfunction "K1_P$2") (pintype "bidirectional"))
      (node (ref "R10") (pin "1") (pinfunction "1_1") (pintype "passive"))
    )
    (net (code "44") (name "L11") (class "Default")
      (node (ref "B6") (pin "P$3") (pinfunction "K2_P$3") (pintype "bidirectional"))
      (node (ref "R9") (pin "1") (pinfunction "1_1") (pintype "passive"))
    )
    (net (code "45") (name "L12") (class "Default")
      (node (ref "B7") (pin "P$2") (pinfunction "K1_P$2") (pintype "bidirectional"))
      (node (ref "R8") (pin "1") (pinfunction "1_1") (pintype "passive"))
    )
    (net (code "46") (name "L13") (class "Default")
      (node (ref "B7") (pin "P$3") (pinfunction "K2_P$3") (pintype "bidirectional"))
      (node (ref "R7") (pin "1") (pinfunction "1_1") (pintype "passive"))
    )
    (net (code "47") (name "L14") (class "Default")
      (node (ref "B8") (pin "P$2") (pinfunction "K1_P$2") (pintype "bidirectional"))
      (node (ref "B8ALT") (pin "P$2") (pinfunction "K1_P$2") (pintype "bidirectional"))
      (node (ref "R6") (pin "1") (pinfunction "1_1") (pintype "passive"))
    )
    (net (code "48") (name "L15") (class "Default")
      (node (ref "B8") (pin "P$3") (pinfunction "K2_P$3") (pintype "bidirectional"))
      (node (ref "B8ALT") (pin "P$3") (pinfunction "K2_P$3") (pintype "bidirectional"))
      (node (ref "R5") (pin "1") (pinfunction "1_1") (pintype "passive"))
    )
    (net (code "49") (name "L16") (class "Default")
      (node (ref "B9") (pin "P$2") (pinfunction "K1_P$2") (pintype "bidirectional"))
      (node (ref "B9ALT") (pin "P$2") (pinfunction "K1_P$2") (pintype "bidirectional"))
      (node (ref "B9ALT1") (pin "P$2") (pinfunction "K1_P$2") (pintype "bidirectional"))
      (node (ref "R32") (pin "1") (pinfunction "1_1") (pintype "passive"))
    )
    (net (code "50") (name "L17") (class "Default")
      (node (ref "B9") (pin "P$3") (pinfunction "K2_P$3") (pintype "bidirectional"))
      (node (ref "B9ALT") (pin "P$3") (pinfunction "K2_P$3") (pintype "bidirectional"))
      (node (ref "B9ALT1") (pin "P$3") (pinfunction "K2_P$3") (pintype "bidirectional"))
      (node (ref "R31") (pin "1") (pinfunction "1_1") (pintype "passive"))
    )
    (net (code "51") (name "Net-(IC2-L0)") (class "Default")
      (node (ref "IC2") (pin "6") (pinfunction "L0_6") (pintype "output"))
      (node (ref "R20") (pin "2") (pinfunction "2_2") (pintype "passive"))
    )
    (net (code "52") (name "Net-(IC2-L1)") (class "Default")
      (node (ref "IC2") (pin "7") (pinfunction "L1_7") (pintype "output"))
      (node (ref "R19") (pin "2") (pinfunction "2_2") (pintype "passive"))
    )
    (net (code "53") (name "Net-(IC2-L2)") (class "Default")
      (node (ref "IC2") (pin "8") (pinfunction "L2_8") (pintype "output"))
      (node (ref "R18") (pin "2") (pinfunction "2_2") (pintype "passive"))
    )
    (net (code "54") (name "Net-(IC2-L3)") (class "Default")
      (node (ref "IC2") (pin "9") (pinfunction "L3_9") (pintype "output"))
      (node (ref "R17") (pin "2") (pinfunction "2_2") (pintype "passive"))
    )
    (net (code "55") (name "Net-(IC2-L4)") (class "Default")
      (node (ref "IC2") (pin "10") (pinfunction "L4_10") (pintype "output"))
      (node (ref "R16") (pin "2") (pinfunction "2_2") (pintype "passive"))
    )
    (net (code "56") (name "Net-(IC2-L5)") (class "Default")
      (node (ref "IC2") (pin "11") (pinfunction "L5_11") (pintype "output"))
      (node (ref "R15") (pin "2") (pinfunction "2_2") (pintype "passive"))
    )
    (net (code "57") (name "Net-(IC2-L6)") (class "Default")
      (node (ref "IC2") (pin "12") (pinfunction "L6_12") (pintype "output"))
      (node (ref "R14") (pin "2") (pinfunction "2_2") (pintype "passive"))
    )
    (net (code "58") (name "Net-(IC2-L7)") (class "Default")
      (node (ref "IC2") (pin "13") (pinfunction "L7_13") (pintype "output"))
      (node (ref "R13") (pin "2") (pinfunction "2_2") (pintype "passive"))
    )
    (net (code "59") (name "Net-(IC2-L8)") (class "Default")
      (node (ref "IC2") (pin "15") (pinfunction "L8_15") (pintype "output"))
      (node (ref "R12") (pin "2") (pinfunction "2_2") (pintype "passive"))
    )
    (net (code "60") (name "Net-(IC2-L9)") (class "Default")
      (node (ref "IC2") (pin "16") (pinfunction "L9_16") (pintype "output"))
      (node (ref "R11") (pin "2") (pinfunction "2_2") (pintype "passive"))
    )
    (net (code "61") (name "Net-(IC2-L10)") (class "Default")
      (node (ref "IC2") (pin "17") (pinfunction "L10_17") (pintype "output"))
      (node (ref "R10") (pin "2") (pinfunction "2_2") (pintype "passive"))
    )
    (net (code "62") (name "Net-(IC2-L11)") (class "Default")
      (node (ref "IC2") (pin "18") (pinfunction "L11_18") (pintype "output"))
      (node (ref "R9") (pin "2") (pinfunction "2_2") (pintype "passive"))
    )
    (net (code "63") (name "Net-(IC2-L12)") (class "Default")
      (node (ref "IC2") (pin "19") (pinfunction "L12_19") (pintype "output"))
      (node (ref "R8") (pin "2") (pinfunction "2_2") (pintype "passive"))
    )
    (net (code "64") (name "Net-(IC2-L13)") (class "Default")
      (node (ref "IC2") (pin "20") (pinfunction "L13_20") (pintype "output"))
      (node (ref "R7") (pin "2") (pinfunction "2_2") (pintype "passive"))
    )
    (net (code "65") (name "Net-(IC2-L14)") (class "Default")
      (node (ref "IC2") (pin "21") (pinfunction "L14_21") (pintype "output"))
      (node (ref "R6") (pin "2") (pinfunction "2_2") (pintype "passive"))
    )
    (net (code "66") (name "Net-(IC2-L15)") (class "Default")
      (node (ref "IC2") (pin "22") (pinfunction "L15_22") (pintype "output"))
      (node (ref "R5") (pin "2") (pinfunction "2_2") (pintype "passive"))
    )
    (net (code "67") (name "Net-(IC3-L0)") (class "Default")
      (node (ref "IC3") (pin "6") (pinfunction "L0_6") (pintype "output"))
      (node (ref "R32") (pin "2") (pinfunction "2_2") (pintype "passive"))
    )
    (net (code "68") (name "Net-(IC3-L1)") (class "Default")
      (node (ref "IC3") (pin "7") (pinfunction "L1_7") (pintype "output"))
      (node (ref "R31") (pin "2") (pinfunction "2_2") (pintype "passive"))
    )
    (net (code "69") (name "SDI_MOSI") (class "Default")
      (node (ref "SERIAL") (pin "8") (pinfunction "8_8") (pintype "passive"))
      (node (ref "SSW1") (pin "6") (pinfunction "SDI_6") (pintype "bidirectional"))
      (node (ref "SSW2") (pin "6") (pinfunction "SDI_6") (pintype "bidirectional"))
      (node (ref "SSW5") (pin "6") (pinfunction "SDI_6") (pintype "bidirectional"))
      (node (ref "SSW5ALT") (pin "6") (pinfunction "SDI_6") (pintype "bidirectional"))
      (node (ref "SSW6") (pin "6") (pinfunction "SDI_6") (pintype "bidirectional"))
      (node (ref "SSW6ALT") (pin "6") (pinfunction "SDI_6") (pintype "bidirectional"))
    )
    (net (code "70") (name "SDI_SCLK") (class "Default")
      (node (ref "SERIAL") (pin "7") (pinfunction "7_7") (pintype "passive"))
      (node (ref "SSW1") (pin "7") (pinfunction "SCK_7") (pintype "bidirectional"))
      (node (ref "SSW2") (pin "7") (pinfunction "SCK_7") (pintype "bidirectional"))
      (node (ref "SSW5") (pin "7") (pinfunction "SCK_7") (pintype "bidirectional"))
      (node (ref "SSW5ALT") (pin "7") (pinfunction "SCK_7") (pintype "bidirectional"))
      (node (ref "SSW6") (pin "7") (pinfunction "SCK_7") (pintype "bidirectional"))
      (node (ref "SSW6ALT") (pin "7") (pinfunction "SCK_7") (pintype "bidirectional"))
    )
    (net (code "71") (name "SLIDER_IN") (class "Default")
      (node (ref "C6") (pin "1") (pinfunction "1_1") (pintype "passive"))
      (node (ref "JP1") (pin "2") (pinfunction "2_2") (pintype "passive"))
      (node (ref "JP2") (pin "2") (pinfunction "2_2") (pintype "passive"))
      (node (ref "POT1") (pin "2A") (pinfunction "S_2A") (pintype "passive"))
      (node (ref "SERIAL") (pin "5") (pinfunction "5_5") (pintype "passive"))
    )
    (net (code "72") (name "unconnected-(IC1-GPB0-Pad1)") (class "Default")
      (node (ref "IC1") (pin "1") (pinfunction "GPB0_1") (pintype "bidirectional"))
    )
    (net (code "73") (name "unconnected-(IC1-GPB1-Pad2)") (class "Default")
      (node (ref "IC1") (pin "2") (pinfunction "GPB1_2") (pintype "bidirectional"))
    )
    (net (code "74") (name "unconnected-(IC1-GPB2-Pad3)") (class "Default")
      (node (ref "IC1") (pin "3") (pinfunction "GPB2_3") (pintype "bidirectional"))
    )
    (net (code "75") (name "unconnected-(IC1-GPB3-Pad4)") (class "Default")
      (node (ref "IC1") (pin "4") (pinfunction "GPB3_4") (pintype "bidirectional"))
    )
    (net (code "76") (name "unconnected-(IC1-GPB5-Pad6)") (class "Default")
      (node (ref "IC1") (pin "6") (pinfunction "GPB5_6") (pintype "bidirectional"))
    )
    (net (code "77") (name "unconnected-(IC1-GPB6-Pad7)") (class "Default")
      (node (ref "IC1") (pin "7") (pinfunction "GPB6_7") (pintype "bidirectional"))
    )
    (net (code "78") (name "unconnected-(IC1-GPB7-Pad8)") (class "Default")
      (node (ref "IC1") (pin "8") (pinfunction "GPB7_8") (pintype "bidirectional"))
    )
    (net (code "79") (name "unconnected-(IC1-INTA-Pad20)") (class "Default")
      (node (ref "IC1") (pin "20") (pinfunction "INTA_20") (pintype "output"))
    )
    (net (code "80") (name "unconnected-(IC1-INTB-Pad19)") (class "Default")
      (node (ref "IC1") (pin "19") (pinfunction "INTB_19") (pintype "output"))
    )
    (net (code "81") (name "unconnected-(IC3-L2-Pad8)") (class "Default")
      (node (ref "IC3") (pin "8") (pinfunction "L2_8") (pintype "output"))
    )
    (net (code "82") (name "unconnected-(IC3-L3-Pad9)") (class "Default")
      (node (ref "IC3") (pin "9") (pinfunction "L3_9") (pintype "output"))
    )
    (net (code "83") (name "unconnected-(IC3-L4-Pad10)") (class "Default")
      (node (ref "IC3") (pin "10") (pinfunction "L4_10") (pintype "output"))
    )
    (net (code "84") (name "unconnected-(IC3-L5-Pad11)") (class "Default")
      (node (ref "IC3") (pin "11") (pinfunction "L5_11") (pintype "output"))
    )
    (net (code "85") (name "unconnected-(IC3-L6-Pad12)") (class "Default")
      (node (ref "IC3") (pin "12") (pinfunction "L6_12") (pintype "output"))
    )
    (net (code "86") (name "unconnected-(IC3-L7-Pad13)") (class "Default")
      (node (ref "IC3") (pin "13") (pinfunction "L7_13") (pintype "output"))
    )
    (net (code "87") (name "unconnected-(IC3-L8-Pad15)") (class "Default")
      (node (ref "IC3") (pin "15") (pinfunction "L8_15") (pintype "output"))
    )
    (net (code "88") (name "unconnected-(IC3-L9-Pad16)") (class "Default")
      (node (ref "IC3") (pin "16") (pinfunction "L9_16") (pintype "output"))
    )
    (net (code "89") (name "unconnected-(IC3-L10-Pad17)") (class "Default")
      (node (ref "IC3") (pin "17") (pinfunction "L10_17") (pintype "output"))
    )
    (net (code "90") (name "unconnected-(IC3-L11-Pad18)") (class "Default")
      (node (ref "IC3") (pin "18") (pinfunction "L11_18") (pintype "output"))
    )
    (net (code "91") (name "unconnected-(IC3-L12-Pad19)") (class "Default")
      (node (ref "IC3") (pin "19") (pinfunction "L12_19") (pintype "output"))
    )
    (net (code "92") (name "unconnected-(IC3-L13-Pad20)") (class "Default")
      (node (ref "IC3") (pin "20") (pinfunction "L13_20") (pintype "output"))
    )
    (net (code "93") (name "unconnected-(IC3-L14-Pad21)") (class "Default")
      (node (ref "IC3") (pin "21") (pinfunction "L14_21") (pintype "output"))
    )
    (net (code "94") (name "unconnected-(IC3-L15-Pad22)") (class "Default")
      (node (ref "IC3") (pin "22") (pinfunction "L15_22") (pintype "output"))
    )
    (net (code "95") (name "unconnected-(IC5-INTA-Pad20)") (class "Default")
      (node (ref "IC5") (pin "20") (pinfunction "INTA_20") (pintype "output"))
    )
    (net (code "96") (name "unconnected-(IC5-INTB-Pad19)") (class "Default")
      (node (ref "IC5") (pin "19") (pinfunction "INTB_19") (pintype "output"))
    )
    (net (code "97") (name "unconnected-(SSW1-SDO-Pad5)") (class "Default")
      (node (ref "SSW1") (pin "5") (pinfunction "SDO_5") (pintype "bidirectional"))
    )
    (net (code "98") (name "unconnected-(SSW2-SDO-Pad5)") (class "Default")
      (node (ref "SSW2") (pin "5") (pinfunction "SDO_5") (pintype "bidirectional"))
    )
    (net (code "99") (name "unconnected-(SSW5-SDO-Pad5)") (class "Default")
      (node (ref "SSW5") (pin "5") (pinfunction "SDO_5") (pintype "bidirectional"))
    )
    (net (code "100") (name "unconnected-(SSW5ALT-SDO-Pad5)") (class "Default")
      (node (ref "SSW5ALT") (pin "5") (pinfunction "SDO_5") (pintype "bidirectional"))
    )
    (net (code "101") (name "unconnected-(SSW6-SDO-Pad5)") (class "Default")
      (node (ref "SSW6") (pin "5") (pinfunction "SDO_5") (pintype "bidirectional"))
    )
    (net (code "102") (name "unconnected-(SSW6ALT-SDO-Pad5)") (class "Default")
      (node (ref "SSW6ALT") (pin "5") (pinfunction "SDO_5") (pintype "bidirectional"))
    )
  )
)
